# Wash_Hand_v1_2-routing.net
KiCad netlist of a schematic drawn in EAGLE
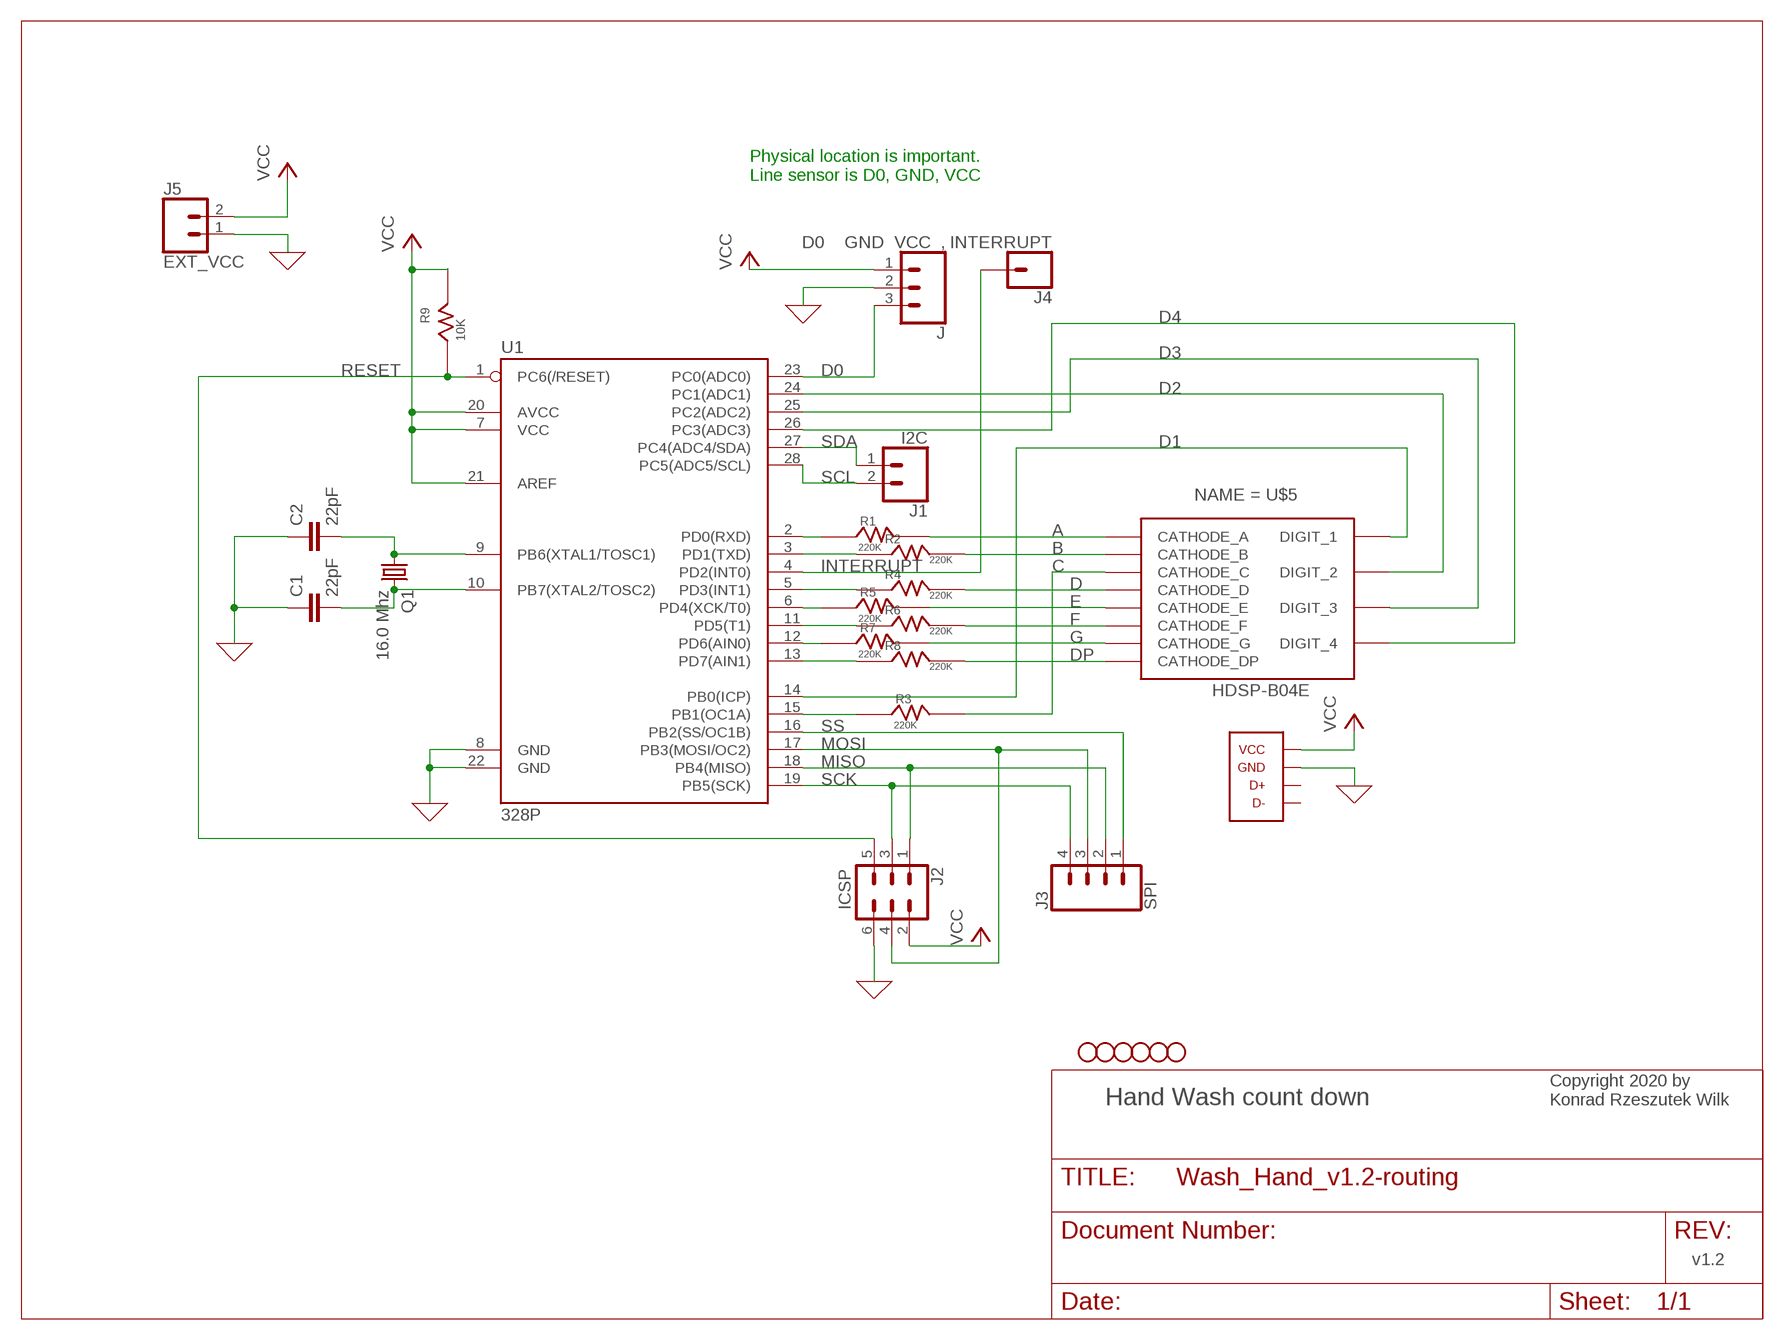
[diagram p0: schematic, sheet 1]

(export (version "E")
  (design (tool "Eeschema 10.0.6"))
  (components
    (comp (ref "C1")
      (value "22pF")
      (footprint "eagle-import:CAP-PTH-2.54")
      (libsource (lib "eagle-import") (part "22PF-PTH-2.54MM-200V-5%"))
    )
    (comp (ref "C2")
      (value "22pF")
      (footprint "eagle-import:CAP-PTH-2.54")
      (libsource (lib "eagle-import") (part "22PF-PTH-2.54MM-200V-5%"))
    )
    (comp (ref "H1")
      (value "STAND-OFF")
      (footprint "eagle-import:STAND-OFF")
      (libsource (lib "eagle-import") (part "STAND-OFF"))
    )
    (comp (ref "H2")
      (value "STAND-OFF")
      (footprint "eagle-import:STAND-OFF")
      (libsource (lib "eagle-import") (part "STAND-OFF"))
    )
    (comp (ref "H3")
      (value "STAND-OFF")
      (footprint "eagle-import:STAND-OFF")
      (libsource (lib "eagle-import") (part "STAND-OFF"))
    )
    (comp (ref "H4")
      (value "STAND-OFF")
      (footprint "eagle-import:STAND-OFF")
      (libsource (lib "eagle-import") (part "STAND-OFF"))
    )
    (comp (ref "H5")
      (value "STAND-OFF")
      (footprint "eagle-import:STAND-OFF")
      (libsource (lib "eagle-import") (part "STAND-OFF"))
    )
    (comp (ref "H6")
      (value "STAND-OFF")
      (footprint "eagle-import:STAND-OFF")
      (libsource (lib "eagle-import") (part "STAND-OFF"))
    )
    (comp (ref "J")
      (value "D0 GND VCC ,")
      (footprint "eagle-import:1X03")
      (libsource (lib "eagle-import") (part "CONN_03"))
    )
    (comp (ref "J1")
      (value "I2C")
      (footprint "eagle-import:1X02")
      (libsource (lib "eagle-import") (part "CONN_02"))
    )
    (comp (ref "J2")
      (value "ICSP")
      (footprint "eagle-import:2X3")
      (libsource (lib "eagle-import") (part "CONN_03X2FEMALE"))
    )
    (comp (ref "J3")
      (value "SPI")
      (footprint "eagle-import:1X04")
      (libsource (lib "eagle-import") (part "CONN_04"))
    )
    (comp (ref "J4")
      (value "INTERRUPT")
      (footprint "eagle-import:1X01")
      (libsource (lib "eagle-import") (part "CONN_01"))
    )
    (comp (ref "J5")
      (value "EXT_VCC")
      (footprint "eagle-import:1X02")
      (libsource (lib "eagle-import") (part "CONN_02"))
    )
    (comp (ref "Q1")
      (value "16.0 Mhz")
      (footprint "eagle-import:HC49_S")
      (libsource (lib "eagle-import") (part "CRYSTALHC49S"))
    )
    (comp (ref "R1")
      (value "220K")
      (footprint "eagle-import:RESISTOR")
      (libsource (lib "eagle-import") (part "RESISTOR"))
    )
    (comp (ref "R2")
      (value "220K")
      (footprint "eagle-import:RESISTOR")
      (libsource (lib "eagle-import") (part "RESISTOR"))
    )
    (comp (ref "R3")
      (value "220K")
      (footprint "eagle-import:RESISTOR")
      (libsource (lib "eagle-import") (part "RESISTOR"))
    )
    (comp (ref "R4")
      (value "220K")
      (footprint "eagle-import:RESISTOR")
      (libsource (lib "eagle-import") (part "RESISTOR"))
    )
    (comp (ref "R5")
      (value "220K")
      (footprint "eagle-import:RESISTOR")
      (libsource (lib "eagle-import") (part "RESISTOR"))
    )
    (comp (ref "R6")
      (value "220K")
      (footprint "eagle-import:RESISTOR")
      (libsource (lib "eagle-import") (part "RESISTOR"))
    )
    (comp (ref "R7")
      (value "220K")
      (footprint "eagle-import:RESISTOR")
      (libsource (lib "eagle-import") (part "RESISTOR"))
    )
    (comp (ref "R8")
      (value "220K")
      (footprint "eagle-import:RESISTOR")
      (libsource (lib "eagle-import") (part "RESISTOR"))
    )
    (comp (ref "R9")
      (value "10K")
      (footprint "eagle-import:RESISTOR")
      (libsource (lib "eagle-import") (part "RESISTOR"))
    )
    (comp (ref "U$4")
      (value "USB_MICROB_10118194_AMPHENOL")
      (footprint "eagle-import:USB_MICROB_10118194_AMPHENOL")
      (libsource (lib "eagle-import") (part "USB_MICROB_10118194_AMPHENOL"))
    )
    (comp (ref "U$5")
      (value "HDSP-B04E")
      (footprint "eagle-import:HDSP-B0XE")
      (libsource (lib "eagle-import") (part "HDSP-B04E"))
    )
    (comp (ref "U1")
      (value "328P")
      (footprint "eagle-import:DIP28")
      (libsource (lib "eagle-import") (part "ATMEGA328P_PDIP"))
    )
  )
  (nets
    (net (code "1") (name "/A") (class "Default")
      (node (ref "R1") (pin "R_2") (pinfunction "R_2_R_2") (pintype "bidirectional"))
      (node (ref "U$5") (pin "PIN$11") (pinfunction "CATHODE_A_PIN$11") (pintype "input"))
    )
    (net (code "2") (name "/B") (class "Default")
      (node (ref "R2") (pin "R_2") (pinfunction "R_2_R_2") (pintype "bidirectional"))
      (node (ref "U$5") (pin "PIN$7") (pinfunction "CATHODE_B_PIN$7") (pintype "input"))
    )
    (net (code "3") (name "/C") (class "Default")
      (node (ref "R3") (pin "R_2") (pinfunction "R_2_R_2") (pintype "bidirectional"))
      (node (ref "U$5") (pin "PIN$4") (pinfunction "CATHODE_C_PIN$4") (pintype "input"))
    )
    (net (code "4") (name "/D") (class "Default")
      (node (ref "R4") (pin "R_2") (pinfunction "R_2_R_2") (pintype "bidirectional"))
      (node (ref "U$5") (pin "PIN$2") (pinfunction "CATHODE_D_PIN$2") (pintype "input"))
    )
    (net (code "5") (name "/D0") (class "Default")
      (node (ref "J") (pin "3") (pinfunction "3_3") (pintype "passive"))
      (node (ref "U1") (pin "23") (pinfunction "PC0(ADC0)_23") (pintype "bidirectional"))
    )
    (net (code "6") (name "/D1") (class "Default")
      (node (ref "U$5") (pin "PIN12") (pinfunction "DIGIT_1_PIN12") (pintype "input"))
      (node (ref "U1") (pin "14") (pinfunction "PB0(ICP)_14") (pintype "bidirectional"))
    )
    (net (code "7") (name "/D2") (class "Default")
      (node (ref "U$5") (pin "PIN$9") (pinfunction "DIGIT_2_PIN$9") (pintype "input"))
      (node (ref "U1") (pin "24") (pinfunction "PC1(ADC1)_24") (pintype "bidirectional"))
    )
    (net (code "8") (name "/D3") (class "Default")
      (node (ref "U$5") (pin "PIN$8") (pinfunction "DIGIT_3_PIN$8") (pintype "input"))
      (node (ref "U1") (pin "25") (pinfunction "PC2(ADC2)_25") (pintype "bidirectional"))
    )
    (net (code "9") (name "/D4") (class "Default")
      (node (ref "U$5") (pin "PIN$6") (pinfunction "DIGIT_4_PIN$6") (pintype "input"))
      (node (ref "U1") (pin "26") (pinfunction "PC3(ADC3)_26") (pintype "bidirectional"))
    )
    (net (code "10") (name "/DP") (class "Default")
      (node (ref "R8") (pin "R_2") (pinfunction "R_2_R_2") (pintype "bidirectional"))
      (node (ref "U$5") (pin "PIN$3") (pinfunction "CATHODE_DP_PIN$3") (pintype "input"))
    )
    (net (code "11") (name "/E") (class "Default")
      (node (ref "R5") (pin "R_2") (pinfunction "R_2_R_2") (pintype "bidirectional"))
      (node (ref "U$5") (pin "PIN$1") (pinfunction "CATHODE_E_PIN$1") (pintype "input"))
    )
    (net (code "12") (name "/F") (class "Default")
      (node (ref "R6") (pin "R_2") (pinfunction "R_2_R_2") (pintype "bidirectional"))
      (node (ref "U$5") (pin "PIN$10") (pinfunction "CATHODE_F_PIN$10") (pintype "input"))
    )
    (net (code "13") (name "/G") (class "Default")
      (node (ref "R7") (pin "R_2") (pinfunction "R_2_R_2") (pintype "bidirectional"))
      (node (ref "U$5") (pin "PIN$5") (pinfunction "CATHODE_G_PIN$5") (pintype "input"))
    )
    (net (code "14") (name "/INTERRUPT") (class "Default")
      (node (ref "J4") (pin "1") (pinfunction "1_1") (pintype "passive"))
      (node (ref "U1") (pin "4") (pinfunction "PD2(INT0)_4") (pintype "bidirectional"))
    )
    (net (code "15") (name "/MISO") (class "Default")
      (node (ref "J2") (pin "1") (pinfunction "1_1") (pintype "bidirectional"))
      (node (ref "J3") (pin "2") (pinfunction "2_2") (pintype "passive"))
      (node (ref "U1") (pin "18") (pinfunction "PB4(MISO)_18") (pintype "bidirectional"))
    )
    (net (code "16") (name "/MOSI") (class "Default")
      (node (ref "J2") (pin "4") (pinfunction "4_4") (pintype "bidirectional"))
      (node (ref "J3") (pin "3") (pinfunction "3_3") (pintype "passive"))
      (node (ref "U1") (pin "17") (pinfunction "PB3(MOSI/OC2)_17") (pintype "bidirectional"))
    )
    (net (code "17") (name "/RESET") (class "Default")
      (node (ref "J2") (pin "5") (pinfunction "5_5") (pintype "bidirectional"))
      (node (ref "R9") (pin "R_1") (pinfunction "R_1_R_1") (pintype "bidirectional"))
      (node (ref "U1") (pin "1") (pinfunction "PC6(/RESET)_1") (pintype "bidirectional"))
    )
    (net (code "18") (name "/SCK") (class "Default")
      (node (ref "J2") (pin "3") (pinfunction "3_3") (pintype "bidirectional"))
      (node (ref "J3") (pin "4") (pinfunction "4_4") (pintype "passive"))
      (node (ref "U1") (pin "19") (pinfunction "PB5(SCK)_19") (pintype "bidirectional"))
    )
    (net (code "19") (name "/SCL") (class "Default")
      (node (ref "J1") (pin "2") (pinfunction "2_2") (pintype "passive"))
      (node (ref "U1") (pin "28") (pinfunction "PC5(ADC5/SCL)_28") (pintype "bidirectional"))
    )
    (net (code "20") (name "/SDA") (class "Default")
      (node (ref "J1") (pin "1") (pinfunction "1_1") (pintype "passive"))
      (node (ref "U1") (pin "27") (pinfunction "PC4(ADC4/SDA)_27") (pintype "bidirectional"))
    )
    (net (code "21") (name "/SS") (class "Default")
      (node (ref "J3") (pin "1") (pinfunction "1_1") (pintype "passive"))
      (node (ref "U1") (pin "16") (pinfunction "PB2(SS/OC1B)_16") (pintype "bidirectional"))
    )
    (net (code "22") (name "GND") (class "Default")
      (node (ref "C1") (pin "1") (pinfunction "1_1") (pintype "passive"))
      (node (ref "C2") (pin "1") (pinfunction "1_1") (pintype "passive"))
      (node (ref "J") (pin "2") (pinfunction "2_2") (pintype "passive"))
      (node (ref "J2") (pin "6") (pinfunction "6_6") (pintype "bidirectional"))
      (node (ref "J5") (pin "1") (pinfunction "1_1") (pintype "passive"))
      (node (ref "U$4") (pin "5") (pinfunction "GND_5") (pintype "bidirectional"))
      (node (ref "U1") (pin "22") (pinfunction "GND_22") (pintype "bidirectional"))
      (node (ref "U1") (pin "8") (pinfunction "GND_8") (pintype "bidirectional"))
    )
    (net (code "23") (name "Net-(U1-PB1(OC1A))") (class "Default")
      (node (ref "R3") (pin "R_1") (pinfunction "R_1_R_1") (pintype "bidirectional"))
      (node (ref "U1") (pin "15") (pinfunction "PB1(OC1A)_15") (pintype "bidirectional"))
    )
    (net (code "24") (name "Net-(U1-PB6(XTAL1{slash}TOSC1))") (class "Default")
      (node (ref "C2") (pin "2") (pinfunction "2_2") (pintype "passive"))
      (node (ref "Q1") (pin "1") (pinfunction "1_1") (pintype "passive"))
      (node (ref "U1") (pin "9") (pinfunction "PB6(XTAL1/TOSC1)_9") (pintype "bidirectional"))
    )
    (net (code "25") (name "Net-(U1-PB7(XTAL2{slash}TOSC2))") (class "Default")
      (node (ref "C1") (pin "2") (pinfunction "2_2") (pintype "passive"))
      (node (ref "Q1") (pin "2") (pinfunction "2_2") (pintype "passive"))
      (node (ref "U1") (pin "10") (pinfunction "PB7(XTAL2/TOSC2)_10") (pintype "bidirectional"))
    )
    (net (code "26") (name "Net-(U1-PD0(RXD))") (class "Default")
      (node (ref "R1") (pin "R_1") (pinfunction "R_1_R_1") (pintype "bidirectional"))
      (node (ref "U1") (pin "2") (pinfunction "PD0(RXD)_2") (pintype "bidirectional"))
    )
    (net (code "27") (name "Net-(U1-PD1(TXD))") (class "Default")
      (node (ref "R2") (pin "R_1") (pinfunction "R_1_R_1") (pintype "bidirectional"))
      (node (ref "U1") (pin "3") (pinfunction "PD1(TXD)_3") (pintype "bidirectional"))
    )
    (net (code "28") (name "Net-(U1-PD3(INT1))") (class "Default")
      (node (ref "R4") (pin "R_1") (pinfunction "R_1_R_1") (pintype "bidirectional"))
      (node (ref "U1") (pin "5") (pinfunction "PD3(INT1)_5") (pintype "bidirectional"))
    )
    (net (code "29") (name "Net-(U1-PD4(XCK{slash}T0))") (class "Default")
      (node (ref "R5") (pin "R_1") (pinfunction "R_1_R_1") (pintype "bidirectional"))
      (node (ref "U1") (pin "6") (pinfunction "PD4(XCK/T0)_6") (pintype "bidirectional"))
    )
    (net (code "30") (name "Net-(U1-PD5(T1))") (class "Default")
      (node (ref "R6") (pin "R_1") (pinfunction "R_1_R_1") (pintype "bidirectional"))
      (node (ref "U1") (pin "11") (pinfunction "PD5(T1)_11") (pintype "bidirectional"))
    )
    (net (code "31") (name "Net-(U1-PD6(AIN0))") (class "Default")
      (node (ref "R7") (pin "R_1") (pinfunction "R_1_R_1") (pintype "bidirectional"))
      (node (ref "U1") (pin "12") (pinfunction "PD6(AIN0)_12") (pintype "bidirectional"))
    )
    (net (code "32") (name "Net-(U1-PD7(AIN1))") (class "Default")
      (node (ref "R8") (pin "R_1") (pinfunction "R_1_R_1") (pintype "bidirectional"))
      (node (ref "U1") (pin "13") (pinfunction "PD7(AIN1)_13") (pintype "bidirectional"))
    )
    (net (code "33") (name "VCC") (class "Default")
      (node (ref "J") (pin "1") (pinfunction "1_1") (pintype "passive"))
      (node (ref "J2") (pin "2") (pinfunction "2_2") (pintype "bidirectional"))
      (node (ref "J5") (pin "2") (pinfunction "2_2") (pintype "passive"))
      (node (ref "R9") (pin "R_2") (pinfunction "R_2_R_2") (pintype "bidirectional"))
      (node (ref "U$4") (pin "1") (pinfunction "VCC_1") (pintype "bidirectional"))
      (node (ref "U1") (pin "20") (pinfunction "AVCC_20") (pintype "bidirectional"))
      (node (ref "U1") (pin "21") (pinfunction "AREF_21") (pintype "bidirectional"))
      (node (ref "U1") (pin "7") (pinfunction "VCC_7") (pintype "bidirectional"))
    )
    (net (code "34") (name "unconnected-(U$4-D+-Pad3)") (class "Default")
      (node (ref "U$4") (pin "3") (pinfunction "D+_3") (pintype "bidirectional"))
    )
    (net (code "35") (name "unconnected-(U$4-D--Pad2)") (class "Default")
      (node (ref "U$4") (pin "2") (pinfunction "D-_2") (pintype "bidirectional"))
    )
  )
)
